# Vernier_Interface_Shield2.net
KiCad netlist of a schematic drawn in EAGLE
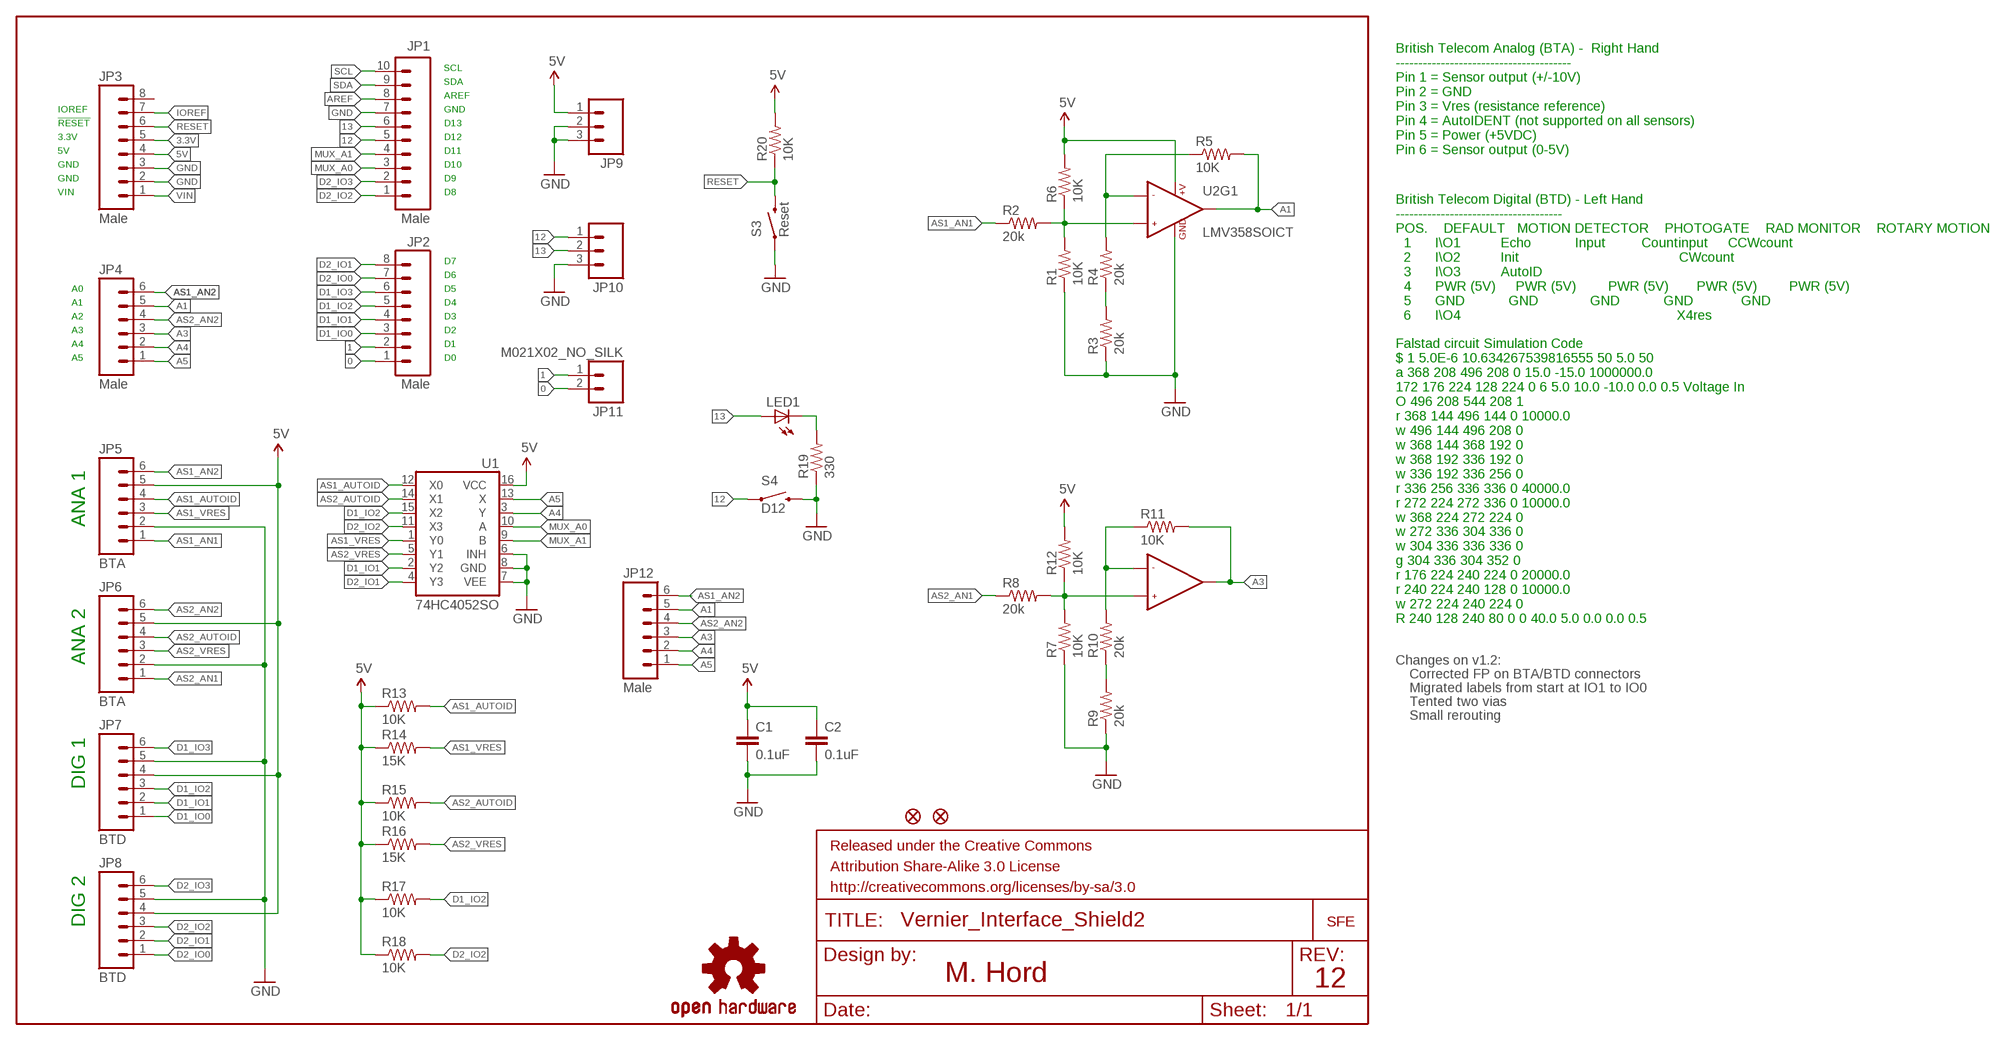
[diagram p0: schematic, sheet 1]

(export (version "E")
  (design (tool "Eeschema 10.0.6"))
  (components
    (comp (ref "C1")
      (value "0.1uF")
      (footprint "eagle-import:0603-CAP")
      (libsource (lib "eagle-import") (part "0.1UF-25V(+80/-20%)(0603)"))
    )
    (comp (ref "C2")
      (value "0.1uF")
      (footprint "eagle-import:0603-CAP")
      (libsource (lib "eagle-import") (part "0.1UF-25V(+80/-20%)(0603)"))
    )
    (comp (ref "FID1")
      (value "FIDUCIALUFIDUCIAL")
      (footprint "eagle-import:MICRO-FIDUCIAL")
      (libsource (lib "eagle-import") (part "FIDUCIALUFIDUCIAL"))
    )
    (comp (ref "FID2")
      (value "FIDUCIALUFIDUCIAL")
      (footprint "eagle-import:MICRO-FIDUCIAL")
      (libsource (lib "eagle-import") (part "FIDUCIALUFIDUCIAL"))
    )
    (comp (ref "FRAME1")
      (value "FRAME-LETTER")
      (footprint "eagle-import:CREATIVE_COMMONS")
      (libsource (lib "eagle-import") (part "FRAME-LETTER"))
    )
    (comp (ref "JP1")
      (value "Male")
      (footprint "eagle-import:1X10_SMD_MALE")
      (libsource (lib "eagle-import") (part "M10SMD_MALE"))
    )
    (comp (ref "JP2")
      (value "Male")
      (footprint "eagle-import:1X08_SMD_MALE")
      (libsource (lib "eagle-import") (part "M08SMD-MALE"))
    )
    (comp (ref "JP3")
      (value "Male")
      (footprint "eagle-import:1X08_SMD_MALE")
      (libsource (lib "eagle-import") (part "M08SMD-MALE"))
    )
    (comp (ref "JP4")
      (value "Male")
      (footprint "eagle-import:1X06_SMD_MALE")
      (libsource (lib "eagle-import") (part "M06SMD_MALE"))
    )
    (comp (ref "JP5")
      (value "BTA")
      (footprint "eagle-import:BTA")
      (libsource (lib "eagle-import") (part "M06VERNIER-ANALOG"))
    )
    (comp (ref "JP6")
      (value "BTA")
      (footprint "eagle-import:BTA")
      (libsource (lib "eagle-import") (part "M06VERNIER-ANALOG"))
    )
    (comp (ref "JP7")
      (value "BTD")
      (footprint "eagle-import:BTD")
      (libsource (lib "eagle-import") (part "M06VERNIER-DIGITAL"))
    )
    (comp (ref "JP8")
      (value "BTD")
      (footprint "eagle-import:BTD")
      (libsource (lib "eagle-import") (part "M06VERNIER-DIGITAL"))
    )
    (comp (ref "JP9")
      (value "M031X03_NO_SILK")
      (footprint "eagle-import:1X03_NO_SILK")
      (libsource (lib "eagle-import") (part "M031X03_NO_SILK"))
    )
    (comp (ref "JP10")
      (value "M031X03_NO_SILK")
      (footprint "eagle-import:1X03_NO_SILK")
      (libsource (lib "eagle-import") (part "M031X03_NO_SILK"))
    )
    (comp (ref "JP11")
      (value "M021X02_NO_SILK")
      (footprint "eagle-import:1X02_NO_SILK")
      (libsource (lib "eagle-import") (part "M021X02_NO_SILK"))
    )
    (comp (ref "JP12")
      (value "Male")
      (footprint "eagle-import:1X06")
      (libsource (lib "eagle-import") (part "M06SIP"))
    )
    (comp (ref "LED1")
      (value "LED5MM")
      (footprint "eagle-import:LED5MM")
      (libsource (lib "eagle-import") (part "LED5MM"))
    )
    (comp (ref "LOGO2")
      (value "OSHW-LOGOS")
      (footprint "eagle-import:OSHW-LOGO-S")
      (libsource (lib "eagle-import") (part "OSHW-LOGOS"))
    )
    (comp (ref "LOGO_1")
      (value "LOGO-SFESK")
      (footprint "eagle-import:SFE-LOGO-FLAME")
      (libsource (lib "eagle-import") (part "LOGO-SFESK"))
    )
    (comp (ref "R1")
      (value "10K")
      (footprint "eagle-import:0603-RES")
      (libsource (lib "eagle-import") (part "10KOHM1/10W1%(0603)0603"))
    )
    (comp (ref "R2")
      (value "20k")
      (footprint "eagle-import:0603-RES")
      (libsource (lib "eagle-import") (part "20KOHM1/10W1%(0603)"))
    )
    (comp (ref "R3")
      (value "20k")
      (footprint "eagle-import:0603-RES")
      (libsource (lib "eagle-import") (part "20KOHM1/10W1%(0603)"))
    )
    (comp (ref "R4")
      (value "20k")
      (footprint "eagle-import:0603-RES")
      (libsource (lib "eagle-import") (part "20KOHM1/10W1%(0603)"))
    )
    (comp (ref "R5")
      (value "10K")
      (footprint "eagle-import:0603-RES")
      (libsource (lib "eagle-import") (part "10KOHM1/10W1%(0603)0603"))
    )
    (comp (ref "R6")
      (value "10K")
      (footprint "eagle-import:0603-RES")
      (libsource (lib "eagle-import") (part "10KOHM1/10W1%(0603)0603"))
    )
    (comp (ref "R7")
      (value "10K")
      (footprint "eagle-import:0603-RES")
      (libsource (lib "eagle-import") (part "10KOHM1/10W1%(0603)0603"))
    )
    (comp (ref "R8")
      (value "20k")
      (footprint "eagle-import:0603-RES")
      (libsource (lib "eagle-import") (part "20KOHM1/10W1%(0603)"))
    )
    (comp (ref "R9")
      (value "20k")
      (footprint "eagle-import:0603-RES")
      (libsource (lib "eagle-import") (part "20KOHM1/10W1%(0603)"))
    )
    (comp (ref "R10")
      (value "20k")
      (footprint "eagle-import:0603-RES")
      (libsource (lib "eagle-import") (part "20KOHM1/10W1%(0603)"))
    )
    (comp (ref "R11")
      (value "10K")
      (footprint "eagle-import:0603-RES")
      (libsource (lib "eagle-import") (part "10KOHM1/10W1%(0603)0603"))
    )
    (comp (ref "R12")
      (value "10K")
      (footprint "eagle-import:0603-RES")
      (libsource (lib "eagle-import") (part "10KOHM1/10W1%(0603)0603"))
    )
    (comp (ref "R13")
      (value "10K")
      (footprint "eagle-import:0603-RES")
      (libsource (lib "eagle-import") (part "10KOHM1/10W1%(0603)0603"))
    )
    (comp (ref "R14")
      (value "15K")
      (footprint "eagle-import:0603-RES")
      (libsource (lib "eagle-import") (part "15KOHM1/10W1%(0603)0603"))
    )
    (comp (ref "R15")
      (value "10K")
      (footprint "eagle-import:0603-RES")
      (libsource (lib "eagle-import") (part "10KOHM1/10W1%(0603)0603"))
    )
    (comp (ref "R16")
      (value "15K")
      (footprint "eagle-import:0603-RES")
      (libsource (lib "eagle-import") (part "15KOHM1/10W1%(0603)0603"))
    )
    (comp (ref "R17")
      (value "10K")
      (footprint "eagle-import:0603-RES")
      (libsource (lib "eagle-import") (part "10KOHM1/10W1%(0603)0603"))
    )
    (comp (ref "R18")
      (value "10K")
      (footprint "eagle-import:0603-RES")
      (libsource (lib "eagle-import") (part "10KOHM1/10W1%(0603)0603"))
    )
    (comp (ref "R19")
      (value "330")
      (footprint "eagle-import:0603-RES")
      (libsource (lib "eagle-import") (part "330OHM1/10W1%(0603)"))
    )
    (comp (ref "R20")
      (value "10K")
      (footprint "eagle-import:0603-RES")
      (libsource (lib "eagle-import") (part "10KOHM1/10W1%(0603)0603"))
    )
    (comp (ref "S3")
      (value "Reset")
      (footprint "eagle-import:TACTILE-PTH")
      (libsource (lib "eagle-import") (part "SWITCH-MOMENTARY-2PTH"))
    )
    (comp (ref "S4")
      (value "D12")
      (footprint "eagle-import:TACTILE-PTH")
      (libsource (lib "eagle-import") (part "SWITCH-MOMENTARY-2PTH"))
    )
    (comp (ref "U1")
      (value "74HC4052SO")
      (footprint "eagle-import:SO16")
      (libsource (lib "eagle-import") (part "74HC4052SO"))
    )
    (comp (ref "U2")
      (value "LMV358SOICT")
      (footprint "eagle-import:SO08-TIGHT")
      (libsource (lib "eagle-import") (part "LMV358SOICT"))
    )
  )
  (nets
    (net (code "1") (name "0") (class "Default")
      (node (ref "JP11") (pin "2") (pinfunction "2_2") (pintype "passive"))
      (node (ref "JP2") (pin "1") (pinfunction "1_1") (pintype "passive"))
    )
    (net (code "2") (name "1") (class "Default")
      (node (ref "JP11") (pin "1") (pinfunction "1_1") (pintype "passive"))
      (node (ref "JP2") (pin "2") (pinfunction "2_2") (pintype "passive"))
    )
    (net (code "3") (name "3.3V") (class "Default")
      (node (ref "JP3") (pin "5") (pinfunction "5_5") (pintype "passive"))
    )
    (net (code "4") (name "5V") (class "Default")
      (node (ref "C1") (pin "1") (pinfunction "1_1") (pintype "passive"))
      (node (ref "C2") (pin "1") (pinfunction "1_1") (pintype "passive"))
      (node (ref "JP3") (pin "4") (pinfunction "4_4") (pintype "passive"))
      (node (ref "JP5") (pin "5") (pinfunction "5_5") (pintype "passive"))
      (node (ref "JP6") (pin "5") (pinfunction "5_5") (pintype "passive"))
      (node (ref "JP7") (pin "4") (pinfunction "4_4") (pintype "passive"))
      (node (ref "JP8") (pin "4") (pinfunction "4_4") (pintype "passive"))
      (node (ref "JP9") (pin "1") (pinfunction "1_1") (pintype "passive"))
      (node (ref "R12") (pin "2") (pinfunction "2_2") (pintype "passive"))
      (node (ref "R13") (pin "1") (pinfunction "1_1") (pintype "passive"))
      (node (ref "R14") (pin "1") (pinfunction "1_1") (pintype "passive"))
      (node (ref "R15") (pin "1") (pinfunction "1_1") (pintype "passive"))
      (node (ref "R16") (pin "1") (pinfunction "1_1") (pintype "passive"))
      (node (ref "R17") (pin "1") (pinfunction "1_1") (pintype "passive"))
      (node (ref "R18") (pin "1") (pinfunction "1_1") (pintype "passive"))
      (node (ref "R20") (pin "2") (pinfunction "2_2") (pintype "passive"))
      (node (ref "R6") (pin "2") (pinfunction "2_2") (pintype "passive"))
      (node (ref "U1") (pin "16") (pinfunction "VCC_16") (pintype "power_in"))
      (node (ref "U2") (pin "8") (pinfunction "+V_8") (pintype "power_in"))
    )
    (net (code "5") (name "12") (class "Default")
      (node (ref "JP1") (pin "5") (pinfunction "5_5") (pintype "passive"))
      (node (ref "JP10") (pin "1") (pinfunction "1_1") (pintype "passive"))
      (node (ref "S4") (pin "1") (pinfunction "1_1") (pintype "passive"))
    )
    (net (code "6") (name "13") (class "Default")
      (node (ref "JP1") (pin "6") (pinfunction "6_6") (pintype "passive"))
      (node (ref "JP10") (pin "2") (pinfunction "2_2") (pintype "passive"))
      (node (ref "LED1") (pin "A") (pinfunction "A_A") (pintype "passive"))
    )
    (net (code "7") (name "A1") (class "Default")
      (node (ref "JP12") (pin "5") (pinfunction "5_5") (pintype "passive"))
      (node (ref "JP4") (pin "5") (pinfunction "5_5") (pintype "passive"))
      (node (ref "R5") (pin "2") (pinfunction "2_2") (pintype "passive"))
      (node (ref "U2") (pin "1") (pinfunction "OUT1_1") (pintype "output"))
    )
    (net (code "8") (name "A3") (class "Default")
      (node (ref "JP12") (pin "3") (pinfunction "3_3") (pintype "passive"))
      (node (ref "JP4") (pin "3") (pinfunction "3_3") (pintype "passive"))
      (node (ref "R11") (pin "2") (pinfunction "2_2") (pintype "passive"))
      (node (ref "U2") (pin "7") (pinfunction "OUT2_7") (pintype "output"))
    )
    (net (code "9") (name "A4") (class "Default")
      (node (ref "JP12") (pin "2") (pinfunction "2_2") (pintype "passive"))
      (node (ref "JP4") (pin "2") (pinfunction "2_2") (pintype "passive"))
      (node (ref "U1") (pin "3") (pinfunction "Y_3") (pintype "bidirectional"))
    )
    (net (code "10") (name "A5") (class "Default")
      (node (ref "JP12") (pin "1") (pinfunction "1_1") (pintype "passive"))
      (node (ref "JP4") (pin "1") (pinfunction "1_1") (pintype "passive"))
      (node (ref "U1") (pin "13") (pinfunction "X_13") (pintype "bidirectional"))
    )
    (net (code "11") (name "AREF") (class "Default")
      (node (ref "JP1") (pin "8") (pinfunction "8_8") (pintype "passive"))
    )
    (net (code "12") (name "AS1_AN1") (class "Default")
      (node (ref "JP5") (pin "1") (pinfunction "1_1") (pintype "passive"))
      (node (ref "R2") (pin "1") (pinfunction "1_1") (pintype "passive"))
    )
    (net (code "13") (name "AS1_AN2") (class "Default")
      (node (ref "JP12") (pin "6") (pinfunction "6_6") (pintype "passive"))
      (node (ref "JP4") (pin "6") (pinfunction "6_6") (pintype "passive"))
      (node (ref "JP5") (pin "6") (pinfunction "6_6") (pintype "passive"))
    )
    (net (code "14") (name "AS1_AUTOID") (class "Default")
      (node (ref "JP5") (pin "4") (pinfunction "4_4") (pintype "passive"))
      (node (ref "R13") (pin "2") (pinfunction "2_2") (pintype "passive"))
      (node (ref "U1") (pin "12") (pinfunction "X0_12") (pintype "bidirectional"))
    )
    (net (code "15") (name "AS1_VRES") (class "Default")
      (node (ref "JP5") (pin "3") (pinfunction "3_3") (pintype "passive"))
      (node (ref "R14") (pin "2") (pinfunction "2_2") (pintype "passive"))
      (node (ref "U1") (pin "1") (pinfunction "Y0_1") (pintype "bidirectional"))
    )
    (net (code "16") (name "AS2_AN1") (class "Default")
      (node (ref "JP6") (pin "1") (pinfunction "1_1") (pintype "passive"))
      (node (ref "R8") (pin "1") (pinfunction "1_1") (pintype "passive"))
    )
    (net (code "17") (name "AS2_AN2") (class "Default")
      (node (ref "JP12") (pin "4") (pinfunction "4_4") (pintype "passive"))
      (node (ref "JP4") (pin "4") (pinfunction "4_4") (pintype "passive"))
      (node (ref "JP6") (pin "6") (pinfunction "6_6") (pintype "passive"))
    )
    (net (code "18") (name "AS2_AUTOID") (class "Default")
      (node (ref "JP6") (pin "4") (pinfunction "4_4") (pintype "passive"))
      (node (ref "R15") (pin "2") (pinfunction "2_2") (pintype "passive"))
      (node (ref "U1") (pin "14") (pinfunction "X1_14") (pintype "bidirectional"))
    )
    (net (code "19") (name "AS2_VRES") (class "Default")
      (node (ref "JP6") (pin "3") (pinfunction "3_3") (pintype "passive"))
      (node (ref "R16") (pin "2") (pinfunction "2_2") (pintype "passive"))
      (node (ref "U1") (pin "5") (pinfunction "Y1_5") (pintype "bidirectional"))
    )
    (net (code "20") (name "D1_IO0") (class "Default")
      (node (ref "JP2") (pin "3") (pinfunction "3_3") (pintype "passive"))
      (node (ref "JP7") (pin "1") (pinfunction "1_1") (pintype "passive"))
    )
    (net (code "21") (name "D1_IO1") (class "Default")
      (node (ref "JP2") (pin "4") (pinfunction "4_4") (pintype "passive"))
      (node (ref "JP7") (pin "2") (pinfunction "2_2") (pintype "passive"))
      (node (ref "U1") (pin "2") (pinfunction "Y2_2") (pintype "bidirectional"))
    )
    (net (code "22") (name "D1_IO2") (class "Default")
      (node (ref "JP2") (pin "5") (pinfunction "5_5") (pintype "passive"))
      (node (ref "JP7") (pin "3") (pinfunction "3_3") (pintype "passive"))
      (node (ref "R17") (pin "2") (pinfunction "2_2") (pintype "passive"))
      (node (ref "U1") (pin "15") (pinfunction "X2_15") (pintype "bidirectional"))
    )
    (net (code "23") (name "D1_IO3") (class "Default")
      (node (ref "JP2") (pin "6") (pinfunction "6_6") (pintype "passive"))
      (node (ref "JP7") (pin "6") (pinfunction "6_6") (pintype "passive"))
    )
    (net (code "24") (name "D2_IO0") (class "Default")
      (node (ref "JP2") (pin "7") (pinfunction "7_7") (pintype "passive"))
      (node (ref "JP8") (pin "1") (pinfunction "1_1") (pintype "passive"))
    )
    (net (code "25") (name "D2_IO1") (class "Default")
      (node (ref "JP2") (pin "8") (pinfunction "8_8") (pintype "passive"))
      (node (ref "JP8") (pin "2") (pinfunction "2_2") (pintype "passive"))
      (node (ref "U1") (pin "4") (pinfunction "Y3_4") (pintype "bidirectional"))
    )
    (net (code "26") (name "D2_IO2") (class "Default")
      (node (ref "JP1") (pin "1") (pinfunction "1_1") (pintype "passive"))
      (node (ref "JP8") (pin "3") (pinfunction "3_3") (pintype "passive"))
      (node (ref "R18") (pin "2") (pinfunction "2_2") (pintype "passive"))
      (node (ref "U1") (pin "11") (pinfunction "X3_11") (pintype "bidirectional"))
    )
    (net (code "27") (name "D2_IO3") (class "Default")
      (node (ref "JP1") (pin "2") (pinfunction "2_2") (pintype "passive"))
      (node (ref "JP8") (pin "6") (pinfunction "6_6") (pintype "passive"))
    )
    (net (code "28") (name "GND") (class "Default")
      (node (ref "C1") (pin "2") (pinfunction "2_2") (pintype "passive"))
      (node (ref "C2") (pin "2") (pinfunction "2_2") (pintype "passive"))
      (node (ref "JP1") (pin "7") (pinfunction "7_7") (pintype "passive"))
      (node (ref "JP10") (pin "3") (pinfunction "3_3") (pintype "passive"))
      (node (ref "JP3") (pin "2") (pinfunction "2_2") (pintype "passive"))
      (node (ref "JP3") (pin "3") (pinfunction "3_3") (pintype "passive"))
      (node (ref "JP5") (pin "2") (pinfunction "2_2") (pintype "passive"))
      (node (ref "JP6") (pin "2") (pinfunction "2_2") (pintype "passive"))
      (node (ref "JP7") (pin "5") (pinfunction "5_5") (pintype "passive"))
      (node (ref "JP8") (pin "5") (pinfunction "5_5") (pintype "passive"))
      (node (ref "JP9") (pin "2") (pinfunction "2_2") (pintype "passive"))
      (node (ref "JP9") (pin "3") (pinfunction "3_3") (pintype "passive"))
      (node (ref "R1") (pin "1") (pinfunction "1_1") (pintype "passive"))
      (node (ref "R19") (pin "1") (pinfunction "1_1") (pintype "passive"))
      (node (ref "R3") (pin "1") (pinfunction "1_1") (pintype "passive"))
      (node (ref "R7") (pin "1") (pinfunction "1_1") (pintype "passive"))
      (node (ref "R9") (pin "1") (pinfunction "1_1") (pintype "passive"))
      (node (ref "S3") (pin "1") (pinfunction "1_1") (pintype "passive"))
      (node (ref "S4") (pin "3") (pinfunction "2_3") (pintype "passive"))
      (node (ref "U1") (pin "6") (pinfunction "INH_6") (pintype "input"))
      (node (ref "U1") (pin "7") (pinfunction "VEE_7") (pintype "power_in"))
      (node (ref "U1") (pin "8") (pinfunction "GND_8") (pintype "power_in"))
      (node (ref "U2") (pin "4") (pinfunction "GND_4") (pintype "power_in"))
    )
    (net (code "29") (name "IOREF") (class "Default")
      (node (ref "JP3") (pin "7") (pinfunction "7_7") (pintype "passive"))
    )
    (net (code "30") (name "MUX_A0") (class "Default")
      (node (ref "JP1") (pin "3") (pinfunction "3_3") (pintype "passive"))
      (node (ref "U1") (pin "10") (pinfunction "A_10") (pintype "input"))
    )
    (net (code "31") (name "MUX_A1") (class "Default")
      (node (ref "JP1") (pin "4") (pinfunction "4_4") (pintype "passive"))
      (node (ref "U1") (pin "9") (pinfunction "B_9") (pintype "input"))
    )
    (net (code "32") (name "Net-(LED1-C)") (class "Default")
      (node (ref "LED1") (pin "K") (pinfunction "C_K") (pintype "passive"))
      (node (ref "R19") (pin "2") (pinfunction "2_2") (pintype "passive"))
    )
    (net (code "33") (name "Net-(R3-Pad2)") (class "Default")
      (node (ref "R3") (pin "2") (pinfunction "2_2") (pintype "passive"))
      (node (ref "R4") (pin "1") (pinfunction "1_1") (pintype "passive"))
    )
    (net (code "34") (name "Net-(R10-Pad1)") (class "Default")
      (node (ref "R10") (pin "1") (pinfunction "1_1") (pintype "passive"))
      (node (ref "R9") (pin "2") (pinfunction "2_2") (pintype "passive"))
    )
    (net (code "35") (name "Net-(U2A-+IN1)") (class "Default")
      (node (ref "R1") (pin "2") (pinfunction "2_2") (pintype "passive"))
      (node (ref "R2") (pin "2") (pinfunction "2_2") (pintype "passive"))
      (node (ref "R6") (pin "1") (pinfunction "1_1") (pintype "passive"))
      (node (ref "U2") (pin "3") (pinfunction "+IN1_3") (pintype "input"))
    )
    (net (code "36") (name "Net-(U2A--IN1)") (class "Default")
      (node (ref "R4") (pin "2") (pinfunction "2_2") (pintype "passive"))
      (node (ref "R5") (pin "1") (pinfunction "1_1") (pintype "passive"))
      (node (ref "U2") (pin "2") (pinfunction "-IN1_2") (pintype "input"))
    )
    (net (code "37") (name "Net-(U2B-+IN2)") (class "Default")
      (node (ref "R12") (pin "1") (pinfunction "1_1") (pintype "passive"))
      (node (ref "R7") (pin "2") (pinfunction "2_2") (pintype "passive"))
      (node (ref "R8") (pin "2") (pinfunction "2_2") (pintype "passive"))
      (node (ref "U2") (pin "5") (pinfunction "+IN2_5") (pintype "input"))
    )
    (net (code "38") (name "Net-(U2B--IN2)") (class "Default")
      (node (ref "R10") (pin "2") (pinfunction "2_2") (pintype "passive"))
      (node (ref "R11") (pin "1") (pinfunction "1_1") (pintype "passive"))
      (node (ref "U2") (pin "6") (pinfunction "-IN2_6") (pintype "input"))
    )
    (net (code "39") (name "RESET") (class "Default")
      (node (ref "JP3") (pin "6") (pinfunction "6_6") (pintype "passive"))
      (node (ref "R20") (pin "1") (pinfunction "1_1") (pintype "passive"))
      (node (ref "S3") (pin "3") (pinfunction "2_3") (pintype "passive"))
    )
    (net (code "40") (name "SCL") (class "Default")
      (node (ref "JP1") (pin "10") (pinfunction "10_10") (pintype "passive"))
    )
    (net (code "41") (name "SDA") (class "Default")
      (node (ref "JP1") (pin "9") (pinfunction "9_9") (pintype "passive"))
    )
    (net (code "42") (name "VIN") (class "Default")
      (node (ref "JP3") (pin "1") (pinfunction "1_1") (pintype "passive"))
    )
    (net (code "43") (name "unconnected-(JP3-Pad8)") (class "Default")
      (node (ref "JP3") (pin "8") (pinfunction "8_8") (pintype "passive"))
    )
  )
)
